# operator_mk3_build_03062015_rev9_dirtyPC.net
KiCad netlist of a schematic drawn in EAGLE
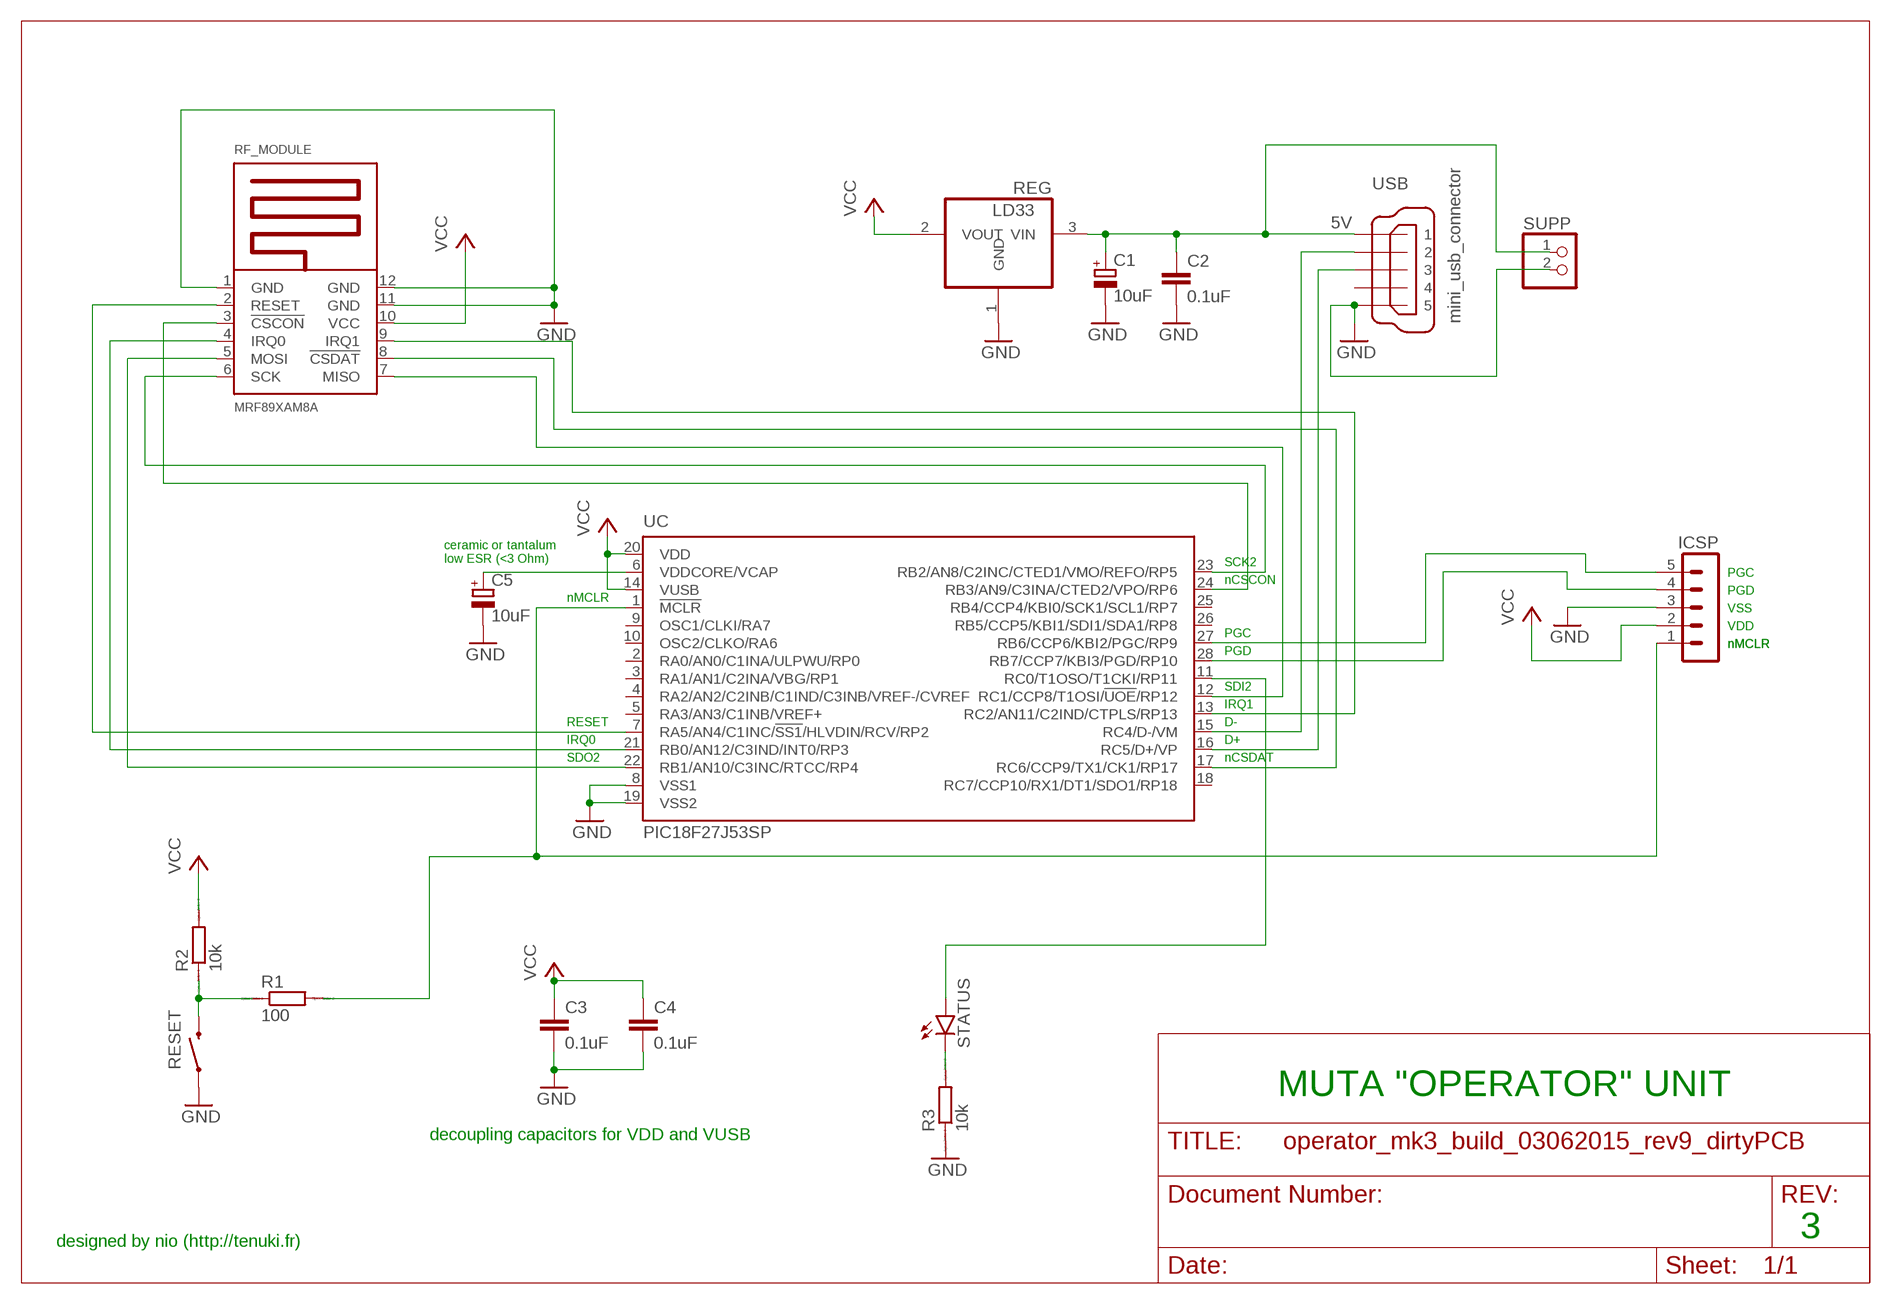
[diagram p0: schematic, sheet 1]

(export (version "E")
  (design (tool "Eeschema 10.0.6"))
  (components
    (comp (ref "C1")
      (value "10uF")
      (footprint "eagle-import:TT5D6")
      (libsource (lib "eagle-import") (part "CPOL-EUTT6D6"))
    )
    (comp (ref "C2")
      (value "0.1uF")
      (footprint "eagle-import:C050-025X075")
      (libsource (lib "eagle-import") (part "C-EU050-025X075"))
    )
    (comp (ref "C3")
      (value "0.1uF")
      (footprint "eagle-import:C050-025X075")
      (libsource (lib "eagle-import") (part "C-EU050-025X075"))
    )
    (comp (ref "C4")
      (value "0.1uF")
      (footprint "eagle-import:C050-025X075")
      (libsource (lib "eagle-import") (part "C-EU050-025X075"))
    )
    (comp (ref "C5")
      (value "10uF")
      (footprint "eagle-import:C_6032-28R")
      (libsource (lib "eagle-import") (part "CPOL-EUC/6032-28R"))
    )
    (comp (ref "ICSP")
      (value "MA05-1")
      (footprint "eagle-import:MA05-1")
      (libsource (lib "eagle-import") (part "MA05-1"))
    )
    (comp (ref "R1")
      (value "100")
      (footprint "eagle-import:0207_10")
      (libsource (lib "eagle-import") (part "R-EU_0207_10"))
    )
    (comp (ref "R2")
      (value "10k")
      (footprint "eagle-import:0207_10")
      (libsource (lib "eagle-import") (part "R-EU_0207_10"))
    )
    (comp (ref "R3")
      (value "10k")
      (footprint "eagle-import:0207_2V")
      (libsource (lib "eagle-import") (part "R-EU_0207_2V"))
    )
    (comp (ref "REG")
      (value "LD33")
      (footprint "eagle-import:SOT223")
      (fields (field (name "MPN") "REG1117") (field (name "MPN_1") "LD33"))
      (libsource (lib "eagle-import") (part "REG1117"))
    )
    (comp (ref "RESET")
      (value "SWITCH-MOMENTARY-2PTH")
      (footprint "eagle-import:TACTILE-PTH")
      (libsource (lib "eagle-import") (part "SWITCH-MOMENTARY-2PTH"))
    )
    (comp (ref "RF_MODULE")
      (value "MRF89XAM8A")
      (footprint "eagle-import:MRF89XAMXA")
      (libsource (lib "eagle-import") (part "MRF89XAM8A"))
    )
    (comp (ref "STATUS")
      (value "LED5MM")
      (footprint "eagle-import:LED5MM")
      (libsource (lib "eagle-import") (part "LED5MM"))
    )
    (comp (ref "SUPP")
      (value "PINHD-1X2")
      (footprint "eagle-import:1X02")
      (libsource (lib "eagle-import") (part "PINHD-1X2"))
    )
    (comp (ref "UC")
      (value "PIC18F27J53SP")
      (footprint "eagle-import:DIL28-3")
      (fields (field (name "MPN") "PIC18F27J53-I/SP"))
      (libsource (lib "eagle-import") (part "PIC18F2J53SP7"))
    )
    (comp (ref "USB")
      (value "mini_usb_connector")
      (footprint "eagle-import:UX60-MB-5ST")
      (libsource (lib "eagle-import") (part "MINI-USB-UX60-MB-5ST"))
    )
  )
  (nets
    (net (code "1") (name "/5V") (class "Default")
      (node (ref "C1") (pin "+") (pinfunction "+_+") (pintype "passive"))
      (node (ref "C2") (pin "1") (pinfunction "1_1") (pintype "passive"))
      (node (ref "REG") (pin "3") (pinfunction "VIN_3") (pintype "input"))
      (node (ref "SUPP") (pin "1") (pinfunction "1_1") (pintype "passive"))
      (node (ref "USB") (pin "1") (pinfunction "1_1") (pintype "input"))
    )
    (net (code "2") (name "GND") (class "Default")
      (node (ref "C1") (pin "-") (pinfunction "-_-") (pintype "passive"))
      (node (ref "C2") (pin "2") (pinfunction "2_2") (pintype "passive"))
      (node (ref "C3") (pin "2") (pinfunction "2_2") (pintype "passive"))
      (node (ref "C4") (pin "2") (pinfunction "2_2") (pintype "passive"))
      (node (ref "C5") (pin "-") (pinfunction "-_-") (pintype "passive"))
      (node (ref "ICSP") (pin "3") (pinfunction "3_3") (pintype "passive"))
      (node (ref "R3") (pin "1") (pinfunction "1_1") (pintype "passive"))
      (node (ref "REG") (pin "1") (pinfunction "GND_1") (pintype "power_in"))
      (node (ref "RESET") (pin "1") (pinfunction "1_1") (pintype "passive"))
      (node (ref "RF_MODULE") (pin "1") (pinfunction "GND_1") (pintype "power_in"))
      (node (ref "RF_MODULE") (pin "11") (pinfunction "GND_11") (pintype "power_in"))
      (node (ref "RF_MODULE") (pin "12") (pinfunction "GND_12") (pintype "power_in"))
      (node (ref "SUPP") (pin "2") (pinfunction "2_2") (pintype "passive"))
      (node (ref "UC") (pin "19") (pinfunction "VSS2_19") (pintype "input"))
      (node (ref "UC") (pin "8") (pinfunction "VSS1_8") (pintype "input"))
      (node (ref "USB") (pin "5") (pinfunction "5_5") (pintype "input"))
    )
    (net (code "3") (name "Net-(RESET-2)") (class "Default")
      (node (ref "R1") (pin "1") (pinfunction "1_1") (pintype "passive"))
      (node (ref "R2") (pin "1") (pinfunction "1_1") (pintype "passive"))
      (node (ref "RESET") (pin "3") (pinfunction "2_3") (pintype "passive"))
    )
    (net (code "4") (name "Net-(RF_MODULE-IRQ0)") (class "Default")
      (node (ref "RF_MODULE") (pin "4") (pinfunction "IRQ0_4") (pintype "output"))
      (node (ref "UC") (pin "21") (pinfunction "RB0/AN12/C3IND/INT0/RP3_21") (pintype "bidirectional"))
    )
    (net (code "5") (name "Net-(RF_MODULE-IRQ1)") (class "Default")
      (node (ref "RF_MODULE") (pin "9") (pinfunction "IRQ1_9") (pintype "output"))
      (node (ref "UC") (pin "13") (pinfunction "RC2/AN11/C2IND/CTPLS/RP13_13") (pintype "bidirectional"))
    )
    (net (code "6") (name "Net-(RF_MODULE-MISO)") (class "Default")
      (node (ref "RF_MODULE") (pin "7") (pinfunction "MISO_7") (pintype "output"))
      (node (ref "UC") (pin "12") (pinfunction "RC1/CCP8/T1OSI/~{UOE}/RP12_12") (pintype "bidirectional"))
    )
    (net (code "7") (name "Net-(RF_MODULE-MOSI)") (class "Default")
      (node (ref "RF_MODULE") (pin "5") (pinfunction "MOSI_5") (pintype "input"))
      (node (ref "UC") (pin "22") (pinfunction "RB1/AN10/C3INC/RTCC/RP4_22") (pintype "bidirectional"))
    )
    (net (code "8") (name "Net-(RF_MODULE-RESET)") (class "Default")
      (node (ref "RF_MODULE") (pin "2") (pinfunction "RESET_2") (pintype "input"))
      (node (ref "UC") (pin "7") (pinfunction "RA5/AN4/C1INC/~{SS1}/HLVDIN/RCV/RP2_7") (pintype "bidirectional"))
    )
    (net (code "9") (name "Net-(RF_MODULE-SCK)") (class "Default")
      (node (ref "RF_MODULE") (pin "6") (pinfunction "SCK_6") (pintype "input"))
      (node (ref "UC") (pin "23") (pinfunction "RB2/AN8/C2INC/CTED1/VMO/REFO/RP5_23") (pintype "bidirectional"))
    )
    (net (code "10") (name "Net-(RF_MODULE-~{CSCON})") (class "Default")
      (node (ref "RF_MODULE") (pin "3") (pinfunction "~{CSCON}_3") (pintype "input"))
      (node (ref "UC") (pin "24") (pinfunction "RB3/AN9/C3INA/CTED2/VPO/RP6_24") (pintype "bidirectional"))
    )
    (net (code "11") (name "Net-(RF_MODULE-~{CSDAT})") (class "Default")
      (node (ref "RF_MODULE") (pin "8") (pinfunction "~{CSDAT}_8") (pintype "input"))
      (node (ref "UC") (pin "17") (pinfunction "RC6/CCP9/TX1/CK1/RP17_17") (pintype "bidirectional"))
    )
    (net (code "12") (name "Net-(STATUS-C)") (class "Default")
      (node (ref "R3") (pin "2") (pinfunction "2_2") (pintype "passive"))
      (node (ref "STATUS") (pin "K") (pinfunction "C_K") (pintype "passive"))
    )
    (net (code "13") (name "Net-(UC-RB6{slash}CCP6{slash}KBI2{slash}PGC{slash}RP9)") (class "Default")
      (node (ref "ICSP") (pin "5") (pinfunction "5_5") (pintype "passive"))
      (node (ref "UC") (pin "27") (pinfunction "RB6/CCP6/KBI2/PGC/RP9_27") (pintype "bidirectional"))
    )
    (net (code "14") (name "Net-(UC-RB7{slash}CCP7{slash}KBI3{slash}PGD{slash}RP10)") (class "Default")
      (node (ref "ICSP") (pin "4") (pinfunction "4_4") (pintype "passive"))
      (node (ref "UC") (pin "28") (pinfunction "RB7/CCP7/KBI3/PGD/RP10_28") (pintype "bidirectional"))
    )
    (net (code "15") (name "Net-(UC-RC0{slash}T1OSO{slash}T1CKI{slash}RP11)") (class "Default")
      (node (ref "STATUS") (pin "A") (pinfunction "A_A") (pintype "passive"))
      (node (ref "UC") (pin "11") (pinfunction "RC0/T1OSO/T1CKI/RP11_11") (pintype "bidirectional"))
    )
    (net (code "16") (name "Net-(UC-RC4{slash}D-{slash}VM)") (class "Default")
      (node (ref "UC") (pin "15") (pinfunction "RC4/D-/VM_15") (pintype "bidirectional"))
      (node (ref "USB") (pin "2") (pinfunction "2_2") (pintype "input"))
    )
    (net (code "17") (name "Net-(UC-RC5{slash}D+{slash}VP)") (class "Default")
      (node (ref "UC") (pin "16") (pinfunction "RC5/D+/VP_16") (pintype "bidirectional"))
      (node (ref "USB") (pin "3") (pinfunction "3_3") (pintype "input"))
    )
    (net (code "18") (name "Net-(UC-VDDCORE{slash}VCAP)") (class "Default")
      (node (ref "C5") (pin "+") (pinfunction "+_+") (pintype "passive"))
      (node (ref "UC") (pin "6") (pinfunction "VDDCORE/VCAP_6") (pintype "input"))
    )
    (net (code "19") (name "Net-(UC-~{MCLR})") (class "Default")
      (node (ref "ICSP") (pin "1") (pinfunction "1_1") (pintype "passive"))
      (node (ref "R1") (pin "2") (pinfunction "2_2") (pintype "passive"))
      (node (ref "UC") (pin "1") (pinfunction "~{MCLR}_1") (pintype "input"))
    )
    (net (code "20") (name "VCC") (class "Default")
      (node (ref "C3") (pin "1") (pinfunction "1_1") (pintype "passive"))
      (node (ref "C4") (pin "1") (pinfunction "1_1") (pintype "passive"))
      (node (ref "ICSP") (pin "2") (pinfunction "2_2") (pintype "passive"))
      (node (ref "R2") (pin "2") (pinfunction "2_2") (pintype "passive"))
      (node (ref "REG") (pin "2") (pinfunction "VOUT_2") (pintype "output"))
      (node (ref "RF_MODULE") (pin "10") (pinfunction "VCC_10") (pintype "power_in"))
      (node (ref "UC") (pin "14") (pinfunction "VUSB_14") (pintype "input"))
      (node (ref "UC") (pin "20") (pinfunction "VDD_20") (pintype "input"))
    )
    (net (code "21") (name "unconnected-(UC-OSC1{slash}CLKI{slash}RA7-Pad9)") (class "Default")
      (node (ref "UC") (pin "9") (pinfunction "OSC1/CLKI/RA7_9") (pintype "bidirectional"))
    )
    (net (code "22") (name "unconnected-(UC-OSC2{slash}CLKO{slash}RA6-Pad10)") (class "Default")
      (node (ref "UC") (pin "10") (pinfunction "OSC2/CLKO/RA6_10") (pintype "bidirectional"))
    )
    (net (code "23") (name "unconnected-(UC-RA0{slash}AN0{slash}C1INA{slash}ULPWU{slash}RP0-Pad2)") (class "Default")
      (node (ref "UC") (pin "2") (pinfunction "RA0/AN0/C1INA/ULPWU/RP0_2") (pintype "bidirectional"))
    )
    (net (code "24") (name "unconnected-(UC-RA1{slash}AN1{slash}C2INA{slash}VBG{slash}RP1-Pad3)") (class "Default")
      (node (ref "UC") (pin "3") (pinfunction "RA1/AN1/C2INA/VBG/RP1_3") (pintype "bidirectional"))
    )
    (net (code "25") (name "unconnected-(UC-RA2{slash}AN2{slash}C2INB{slash}C1IND{slash}C3INB{slash}VREF-{slash}CVREF-Pad4)") (class "Default")
      (node (ref "UC") (pin "4") (pinfunction "RA2/AN2/C2INB/C1IND/C3INB/VREF-/CVREF_4") (pintype "bidirectional"))
    )
    (net (code "26") (name "unconnected-(UC-RA3{slash}AN3{slash}C1INB{slash}VREF+-Pad5)") (class "Default")
      (node (ref "UC") (pin "5") (pinfunction "RA3/AN3/C1INB/VREF+_5") (pintype "bidirectional"))
    )
    (net (code "27") (name "unconnected-(UC-RB4{slash}CCP4{slash}KBI0{slash}SCK1{slash}SCL1{slash}RP7-Pad25)") (class "Default")
      (node (ref "UC") (pin "25") (pinfunction "RB4/CCP4/KBI0/SCK1/SCL1/RP7_25") (pintype "bidirectional"))
    )
    (net (code "28") (name "unconnected-(UC-RB5{slash}CCP5{slash}KBI1{slash}SDI1{slash}SDA1{slash}RP8-Pad26)") (class "Default")
      (node (ref "UC") (pin "26") (pinfunction "RB5/CCP5/KBI1/SDI1/SDA1/RP8_26") (pintype "bidirectional"))
    )
    (net (code "29") (name "unconnected-(UC-RC7{slash}CCP10{slash}RX1{slash}DT1{slash}SDO1{slash}RP18-Pad18)") (class "Default")
      (node (ref "UC") (pin "18") (pinfunction "RC7/CCP10/RX1/DT1/SDO1/RP18_18") (pintype "bidirectional"))
    )
    (net (code "30") (name "unconnected-(USB-Pad4)") (class "Default")
      (node (ref "USB") (pin "4") (pinfunction "4_4") (pintype "input"))
    )
  )
)
